# Charger.net
KiCad netlist of a schematic drawn in Altium Designer
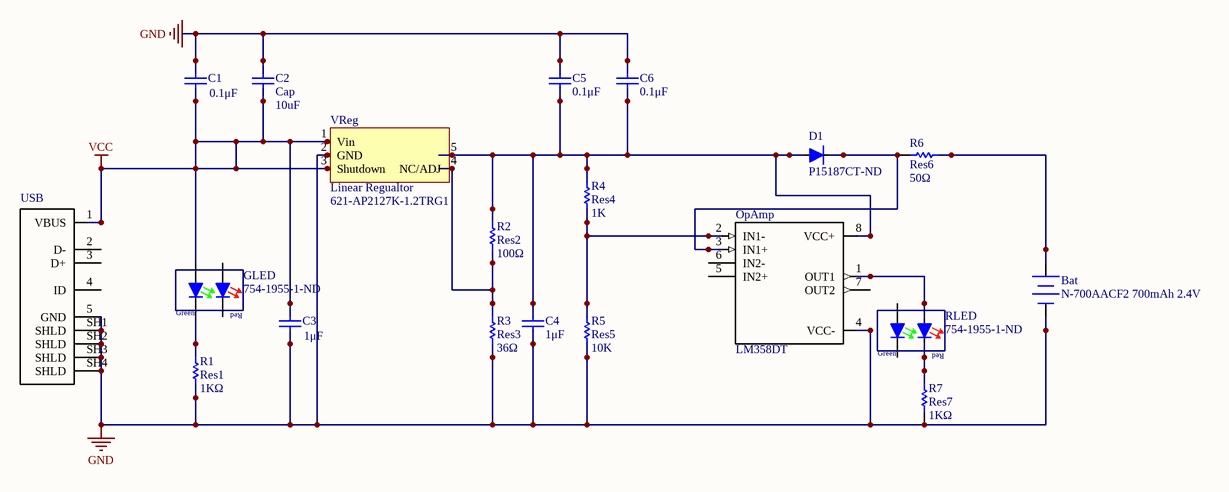
[diagram p0: Charger.SchDoc]

(export (version "E")
  (design (tool "Eeschema 10.0.6"))
  (components
    (comp (ref "Bat")
      (value "N-700AACF2 700mAh 2.4V")
      (footprint "*FCI_10118193-0001LF_10118193-0001LF(Primary)")
      (description "Multicell Battery")
      (fields (field (name "PUBLISHER") "Altium Limited"))
      (libsource (lib "Miscellaneous Devices") (part "Battery"))
    )
    (comp (ref "C1")
      (value "0.1μF")
      (footprint "CAPC1608N(0603\")")
      (description "Capacitor, Ceramic, 16V, +/- 10%, 0603 SMD, X7R")
      (fields (field (name "PUBLISHER") "AUVic") (field (name "CREATED BY") "Andy Bates"))
      (libsource (lib "AUVic_Integrated_Library_Capacitors") (part "0.1uF 16V 0603 SMD, Ceramic"))
    )
    (comp (ref "C2")
      (value "Cap")
      (footprint "CAPC2012N(0805\")")
      (description "Capacitor")
      (fields (field (name "ALTIUM_VALUE") "10uF") (field (name "PUBLISHER") "Altium Limited"))
      (libsource (lib "Miscellaneous Devices") (part "Cap"))
    )
    (comp (ref "C3")
      (value "1μF")
      (footprint "CAPC1608N(0603\")")
      (description "Capacitor, Ceramic, 25V, +/- 10%, 0603 SMD, X5R")
      (fields
        (field (name "MFG") "Murata-Electronics-North-America")
        (field (name "PUBLISHER") "AUVic")
        (field (name "CREATED BY") "Andy Bates")
      )
      (libsource (lib "AUVic_Integrated_Library_Capacitors") (part "1uF 25V 0603 SMD, Ceramic"))
    )
    (comp (ref "C4")
      (value "1μF")
      (footprint "CAPC1608N(0603\")")
      (description "Capacitor, Ceramic, 25V, +/- 10%, 0603 SMD, X5R")
      (fields
        (field (name "MFG") "Murata-Electronics-North-America")
        (field (name "PUBLISHER") "AUVic")
        (field (name "CREATED BY") "Andy Bates")
      )
      (libsource (lib "AUVic_Integrated_Library_Capacitors") (part "1uF 25V 0603 SMD, Ceramic"))
    )
    (comp (ref "C5")
      (value "0.1μF")
      (footprint "CAPC1608N(0603\")")
      (description "Capacitor, Ceramic, 16V, +/- 10%, 0603 SMD, X7R")
      (fields (field (name "PUBLISHER") "AUVic") (field (name "CREATED BY") "Andy Bates"))
      (libsource (lib "AUVic_Integrated_Library_Capacitors") (part "0.1uF 16V 0603 SMD, Ceramic"))
    )
    (comp (ref "C6")
      (value "0.1μF")
      (footprint "CAPC1608N(0603\")")
      (description "Capacitor, Ceramic, 16V, +/- 10%, 0603 SMD, X7R")
      (fields (field (name "PUBLISHER") "AUVic") (field (name "CREATED BY") "Andy Bates"))
      (libsource (lib "AUVic_Integrated_Library_Capacitors") (part "0.1uF 16V 0603 SMD, Ceramic"))
    )
    (comp (ref "D1")
      (value "DA2S10400L, SOD323F / SC-90")
      (footprint "SODFL535X110-2N")
      (fields
        (field (name "SUPPLIER PART NUMBER 1") "P15187CT-ND")
        (field (name "CREATED BY") "Andy Bates")
        (field (name "PUBLISHER") "AUVic")
      )
      (libsource (lib "AUVic_Integrated_Library_Diodes") (part "DA2S10400L, SOD323F / SC-90"))
    )
    (comp (ref "GLED")
      (value "~")
      (footprint "LED0603_DUAL")
      (description "LED, 0603 (1608), Red/Green, Clear")
      (fields
        (field (name "SUPPLIER PART NUMBER 1") "754-1955-1-ND")
        (field (name "CREATED BY") "Ashwin Sira")
      )
      (libsource (lib "AUVic_Integrated_Library_Diodes") (part "LED, 0603 (1608), Red/Green, Clear"))
    )
    (comp (ref "OpAmp")
      (value "LM358DT")
      (footprint "*SOIC127P600X175-8N")
      (description "LM358 Series 30 V 1.1 MHz Low Power Dual Operational Amplifier - SOIC-8")
      (fields (field (name "MF") "STMicroelectronics"))
      (libsource (lib "LM358DT") (part "LM358DT"))
    )
    (comp (ref "R1")
      (value "Res1")
      (footprint "RESC1608N(0603\")")
      (description "Resistor")
      (fields (field (name "ALTIUM_VALUE") "1KΩ") (field (name "PUBLISHER") "Altium Limited"))
      (libsource (lib "Miscellaneous Devices") (part "Res1"))
    )
    (comp (ref "R2")
      (value "Res2")
      (footprint "RESC1608N(0603\")")
      (description "Resistor")
      (fields (field (name "ALTIUM_VALUE") "100Ω") (field (name "PUBLISHER") "Altium Limited"))
      (libsource (lib "Miscellaneous Devices") (part "Res1"))
    )
    (comp (ref "R3")
      (value "Res3")
      (footprint "RESC1608N(0603\")")
      (description "Resistor")
      (fields (field (name "ALTIUM_VALUE") "36Ω") (field (name "PUBLISHER") "Altium Limited"))
      (libsource (lib "Miscellaneous Devices") (part "Res1"))
    )
    (comp (ref "R4")
      (value "Res4")
      (footprint "RESC1608N(0603\")")
      (description "Resistor")
      (fields (field (name "ALTIUM_VALUE") "1K") (field (name "PUBLISHER") "Altium Limited"))
      (libsource (lib "Miscellaneous Devices") (part "Res1"))
    )
    (comp (ref "R5")
      (value "Res5")
      (footprint "RESC1608N(0603\")")
      (description "Resistor")
      (fields (field (name "ALTIUM_VALUE") "10K") (field (name "PUBLISHER") "Altium Limited"))
      (libsource (lib "Miscellaneous Devices") (part "Res1"))
    )
    (comp (ref "R6")
      (value "Res6")
      (footprint "RESC1608N(0603\")")
      (description "Resistor")
      (fields (field (name "ALTIUM_VALUE") "50Ω") (field (name "PUBLISHER") "Altium Limited"))
      (libsource (lib "Miscellaneous Devices") (part "Res1"))
    )
    (comp (ref "R7")
      (value "Res7")
      (footprint "RESC1608N(0603\")")
      (description "Resistor")
      (fields (field (name "ALTIUM_VALUE") "1KΩ") (field (name "PUBLISHER") "Altium Limited"))
      (libsource (lib "Miscellaneous Devices") (part "Res1"))
    )
    (comp (ref "RLED")
      (value "~")
      (footprint "LED0603_DUAL")
      (description "LED, 0603 (1608), Red/Green, Clear")
      (fields
        (field (name "SUPPLIER PART NUMBER 1") "754-1955-1-ND")
        (field (name "CREATED BY") "Ashwin Sira")
      )
      (libsource (lib "AUVic_Integrated_Library_Diodes") (part "LED, 0603 (1608), Red/Green, Clear"))
    )
    (comp (ref "USB")
      (value "1734035-3")
      (footprint "*TE_1734035-3_1734035-3(Primary)")
      (description "Conn Mini USB 2.0 Type B RCP 5 POS 0.8mm Solder RA SMD 5 Terminal 1 Port T/R")
      (fields (field (name "MF") "TE Connectivity"))
      (libsource (lib "1734035-3") (part "1734035-3"))
    )
    (comp (ref "VReg")
      (value "Linear Regualtor")
      (footprint "621-AP2127K-1.2TRG1")
      (fields (field (name "SUPPLIER PART NUMBER 1") "621-AP2127K-1.2TRG1"))
      (libsource (lib "Pinger Library") (part "Linear Regualtor"))
    )
  )
  (nets
    (net (code "1") (name "GND") (class "Default")
      (node (ref "Bat") (pin "2") (pinfunction "-_2") (pintype "passive"))
      (node (ref "C1") (pin "2") (pinfunction "Cathode_2") (pintype "passive"))
      (node (ref "C2") (pin "2") (pinfunction "2_2") (pintype "passive"))
      (node (ref "C3") (pin "1") (pinfunction "Anode_1") (pintype "passive"))
      (node (ref "C4") (pin "1") (pinfunction "Anode_1") (pintype "passive"))
      (node (ref "C5") (pin "2") (pinfunction "Cathode_2") (pintype "passive"))
      (node (ref "C6") (pin "2") (pinfunction "Cathode_2") (pintype "passive"))
      (node (ref "OpAmp") (pin "4") (pinfunction "VCC-_4") (pintype "passive"))
      (node (ref "R1") (pin "1") (pinfunction "1_1") (pintype "passive"))
      (node (ref "R3") (pin "1") (pinfunction "1_1") (pintype "passive"))
      (node (ref "R5") (pin "1") (pinfunction "1_1") (pintype "passive"))
      (node (ref "R7") (pin "1") (pinfunction "1_1") (pintype "passive"))
      (node (ref "USB") (pin "5") (pinfunction "GND_5") (pintype "passive"))
      (node (ref "USB") (pin "SH1") (pinfunction "SHLD_SH1") (pintype "passive"))
      (node (ref "USB") (pin "SH2") (pinfunction "SHLD_SH2") (pintype "passive"))
      (node (ref "USB") (pin "SH3") (pinfunction "SHLD_SH3") (pintype "passive"))
      (node (ref "USB") (pin "SH4") (pinfunction "SHLD_SH4") (pintype "passive"))
      (node (ref "VReg") (pin "2") (pinfunction "GND_2") (pintype "passive"))
    )
    (net (code "2") (name "Net-(Bat-+)") (class "Default")
      (node (ref "Bat") (pin "1") (pinfunction "+_1") (pintype "passive"))
      (node (ref "R6") (pin "2") (pinfunction "2_2") (pintype "passive"))
    )
    (net (code "3") (name "Net-(C4-Cathode)") (class "Default")
      (node (ref "C4") (pin "2") (pinfunction "Cathode_2") (pintype "passive"))
      (node (ref "C5") (pin "1") (pinfunction "Anode_1") (pintype "passive"))
      (node (ref "C6") (pin "1") (pinfunction "Anode_1") (pintype "passive"))
      (node (ref "D1") (pin "1") (pinfunction "Anode_1") (pintype "passive"))
      (node (ref "OpAmp") (pin "8") (pinfunction "VCC+_8") (pintype "passive"))
      (node (ref "R2") (pin "2") (pinfunction "2_2") (pintype "passive"))
      (node (ref "R4") (pin "2") (pinfunction "2_2") (pintype "passive"))
      (node (ref "VReg") (pin "5") (pinfunction "Vout_5") (pintype "power_in"))
    )
    (net (code "4") (name "Net-(D1-Cathode)") (class "Default")
      (node (ref "D1") (pin "2") (pinfunction "Cathode_2") (pintype "passive"))
      (node (ref "OpAmp") (pin "3") (pinfunction "IN1+_3") (pintype "input"))
      (node (ref "R6") (pin "1") (pinfunction "1_1") (pintype "passive"))
    )
    (net (code "5") (name "Net-(GLED-Anode-Pad2)") (class "Default")
      (node (ref "GLED") (pin "2") (pinfunction "Anode_2") (pintype "passive"))
      (node (ref "R1") (pin "2") (pinfunction "2_2") (pintype "passive"))
    )
    (net (code "6") (name "Net-(OpAmp-IN1-)") (class "Default")
      (node (ref "OpAmp") (pin "2") (pinfunction "IN1-_2") (pintype "input"))
      (node (ref "R4") (pin "1") (pinfunction "1_1") (pintype "passive"))
      (node (ref "R5") (pin "2") (pinfunction "2_2") (pintype "passive"))
    )
    (net (code "7") (name "Net-(OpAmp-OUT1)") (class "Default")
      (node (ref "OpAmp") (pin "1") (pinfunction "OUT1_1") (pintype "output"))
      (node (ref "RLED") (pin "4") (pinfunction "Cathode_4") (pintype "passive"))
    )
    (net (code "8") (name "Net-(R7-Pad2)") (class "Default")
      (node (ref "R7") (pin "2") (pinfunction "2_2") (pintype "passive"))
      (node (ref "RLED") (pin "3") (pinfunction "Anode_3") (pintype "passive"))
    )
    (net (code "9") (name "Net-(VReg-NC{slash}ADJ)") (class "Default")
      (node (ref "R2") (pin "1") (pinfunction "1_1") (pintype "passive"))
      (node (ref "R3") (pin "2") (pinfunction "2_2") (pintype "passive"))
      (node (ref "VReg") (pin "4") (pinfunction "NC/ADJ_4") (pintype "input"))
    )
    (net (code "10") (name "VCC") (class "Default")
      (node (ref "C1") (pin "1") (pinfunction "Anode_1") (pintype "passive"))
      (node (ref "C2") (pin "1") (pinfunction "1_1") (pintype "passive"))
      (node (ref "C3") (pin "2") (pinfunction "Cathode_2") (pintype "passive"))
      (node (ref "GLED") (pin "1") (pinfunction "Cathode_1") (pintype "passive"))
      (node (ref "USB") (pin "1") (pinfunction "VBUS_1") (pintype "passive"))
      (node (ref "VReg") (pin "1") (pinfunction "Vin_1") (pintype "input"))
      (node (ref "VReg") (pin "3") (pinfunction "Shutdown_3") (pintype "input"))
    )
    (net (code "11") (name "unconnected-(GLED-Anode-Pad3)") (class "Default")
      (node (ref "GLED") (pin "3") (pinfunction "Anode_3") (pintype "passive"))
    )
    (net (code "12") (name "unconnected-(GLED-Cathode-Pad4)") (class "Default")
      (node (ref "GLED") (pin "4") (pinfunction "Cathode_4") (pintype "passive"))
    )
    (net (code "13") (name "unconnected-(OpAmp-IN2+-Pad5)") (class "Default")
      (node (ref "OpAmp") (pin "5") (pinfunction "IN2+_5") (pintype "passive"))
    )
    (net (code "14") (name "unconnected-(OpAmp-IN2--Pad6)") (class "Default")
      (node (ref "OpAmp") (pin "6") (pinfunction "IN2-_6") (pintype "passive"))
    )
    (net (code "15") (name "unconnected-(OpAmp-OUT2-Pad7)") (class "Default")
      (node (ref "OpAmp") (pin "7") (pinfunction "OUT2_7") (pintype "output"))
    )
    (net (code "16") (name "unconnected-(RLED-Anode-Pad2)") (class "Default")
      (node (ref "RLED") (pin "2") (pinfunction "Anode_2") (pintype "passive"))
    )
    (net (code "17") (name "unconnected-(RLED-Cathode-Pad1)") (class "Default")
      (node (ref "RLED") (pin "1") (pinfunction "Cathode_1") (pintype "passive"))
    )
    (net (code "18") (name "unconnected-(USB-D+-Pad3)") (class "Default")
      (node (ref "USB") (pin "3") (pinfunction "D+_3") (pintype "passive"))
    )
    (net (code "19") (name "unconnected-(USB-D--Pad2)") (class "Default")
      (node (ref "USB") (pin "2") (pinfunction "D-_2") (pintype "passive"))
    )
    (net (code "20") (name "unconnected-(USB-ID-Pad4)") (class "Default")
      (node (ref "USB") (pin "4") (pinfunction "ID_4") (pintype "passive"))
    )
  )
)
